# OpenDeck.net
KiCad netlist of a schematic drawn in EAGLE
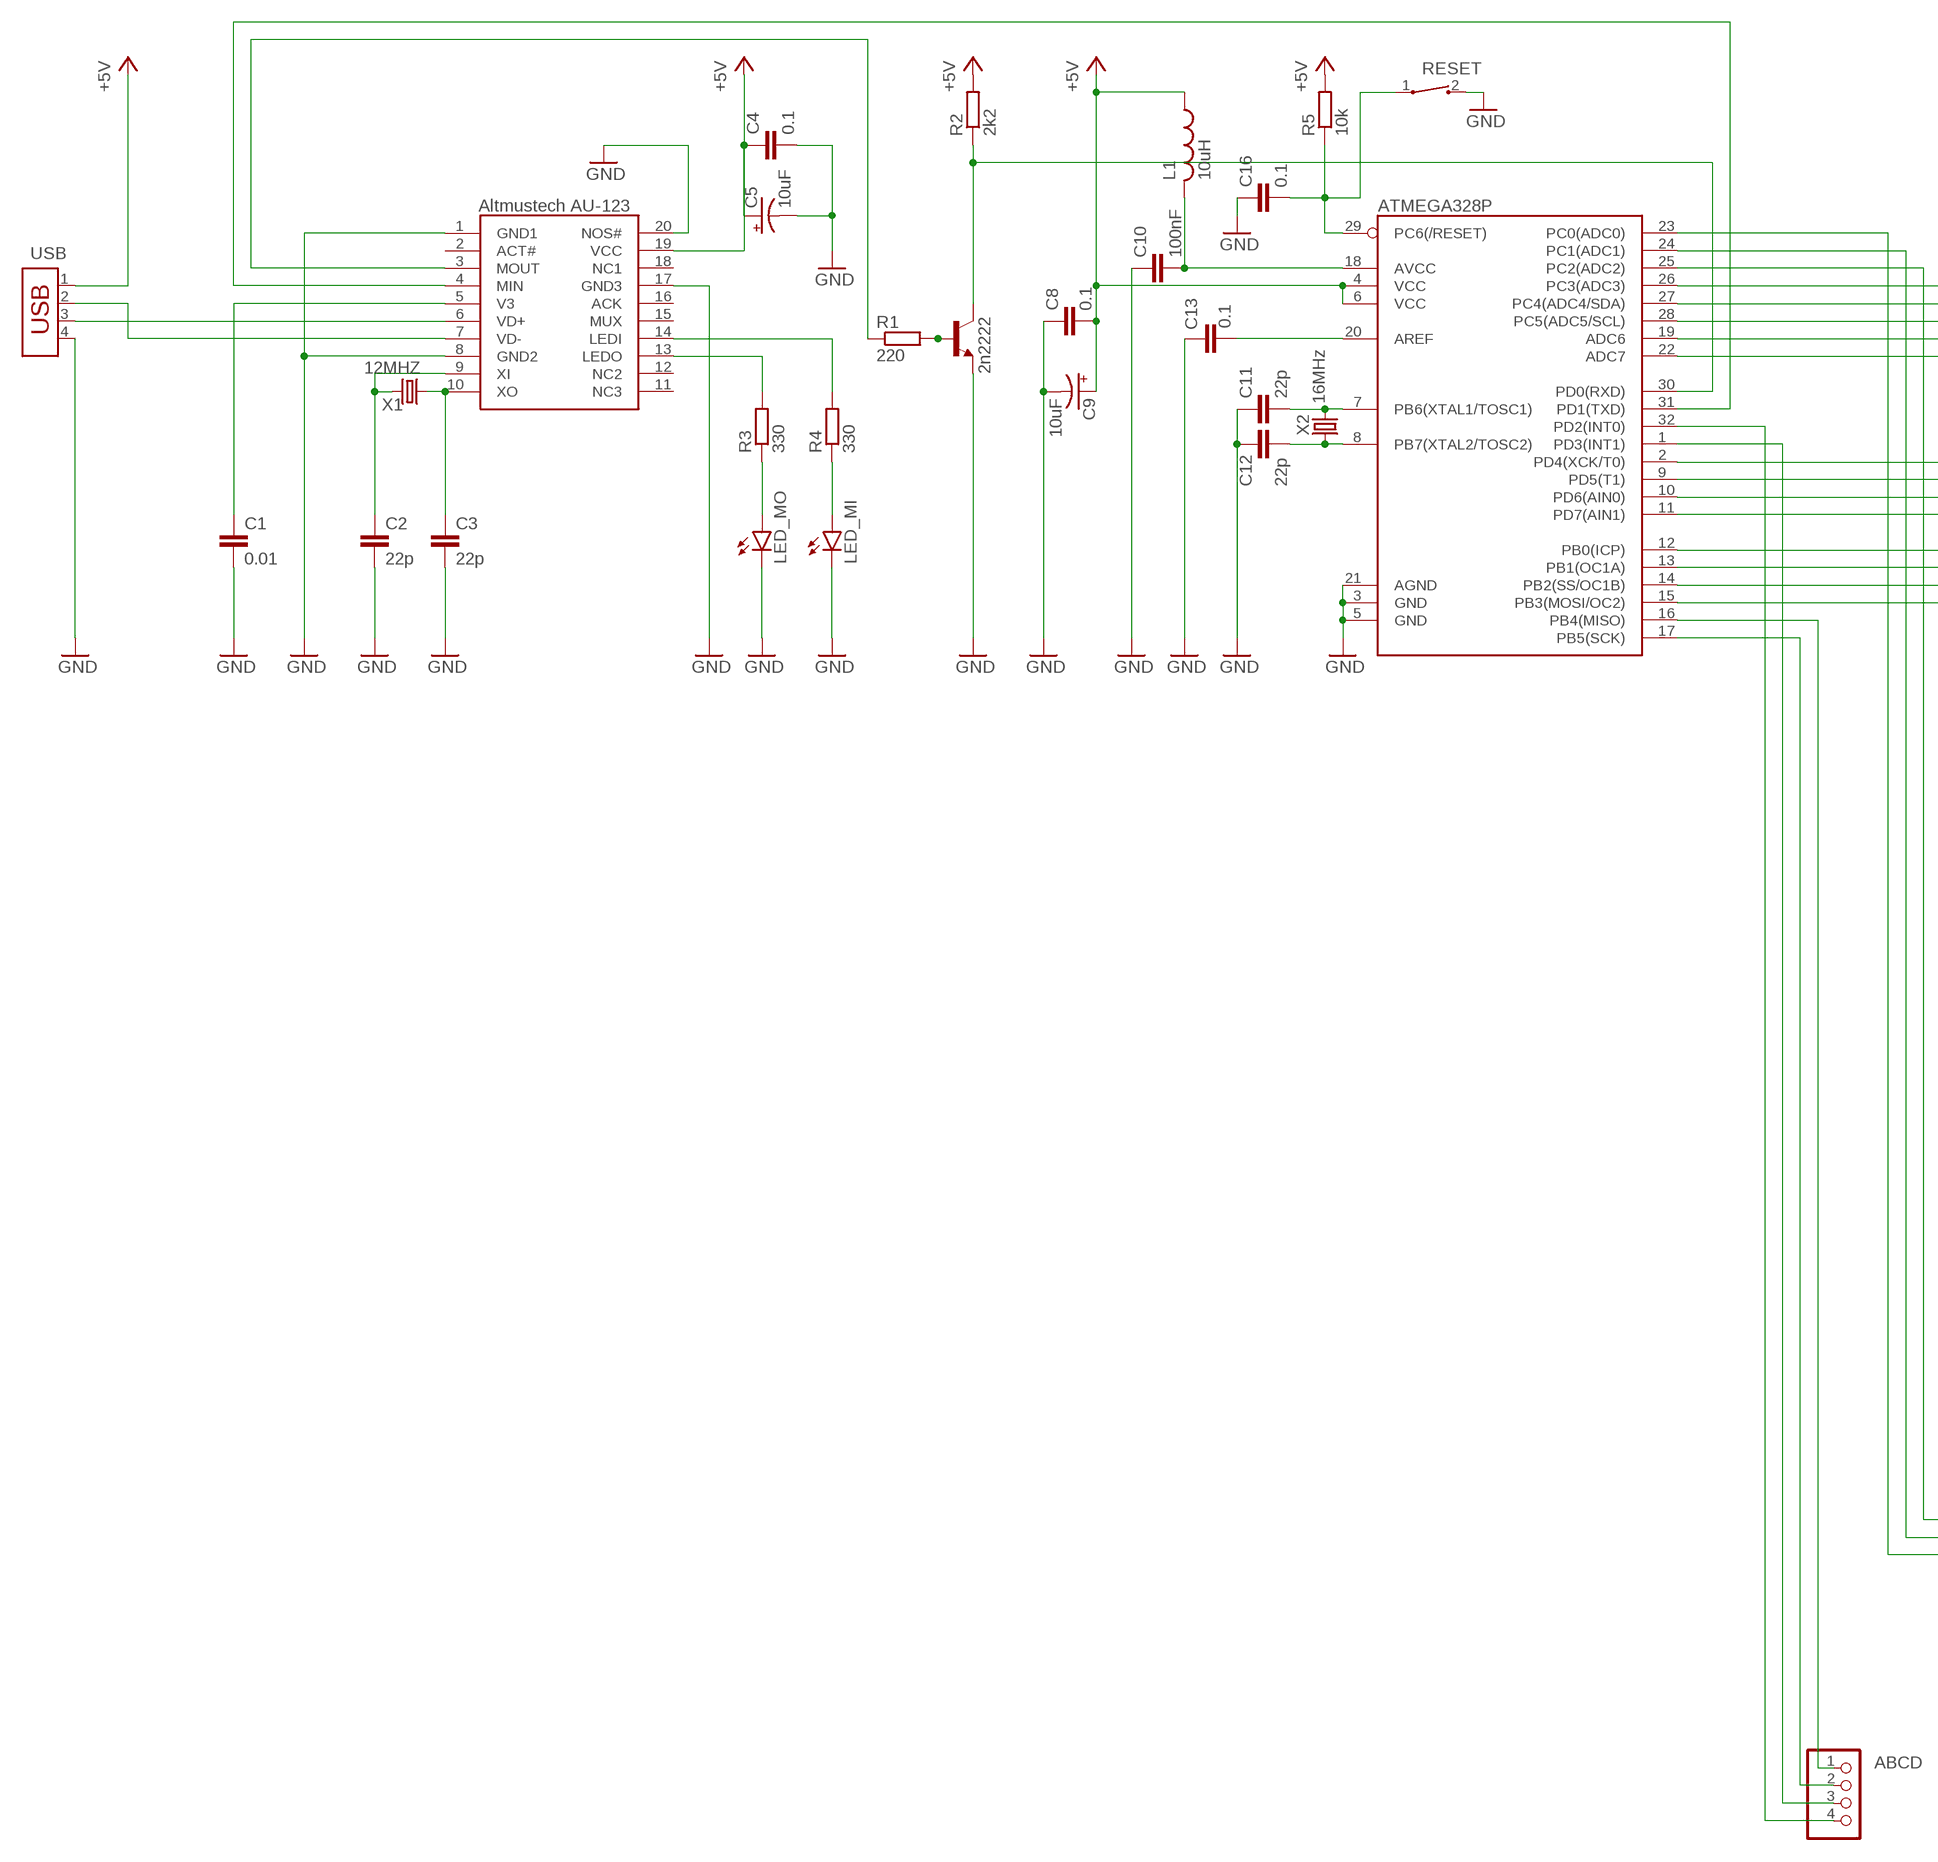
[diagram p0: schematic, sheet 1, part 1 of 2]
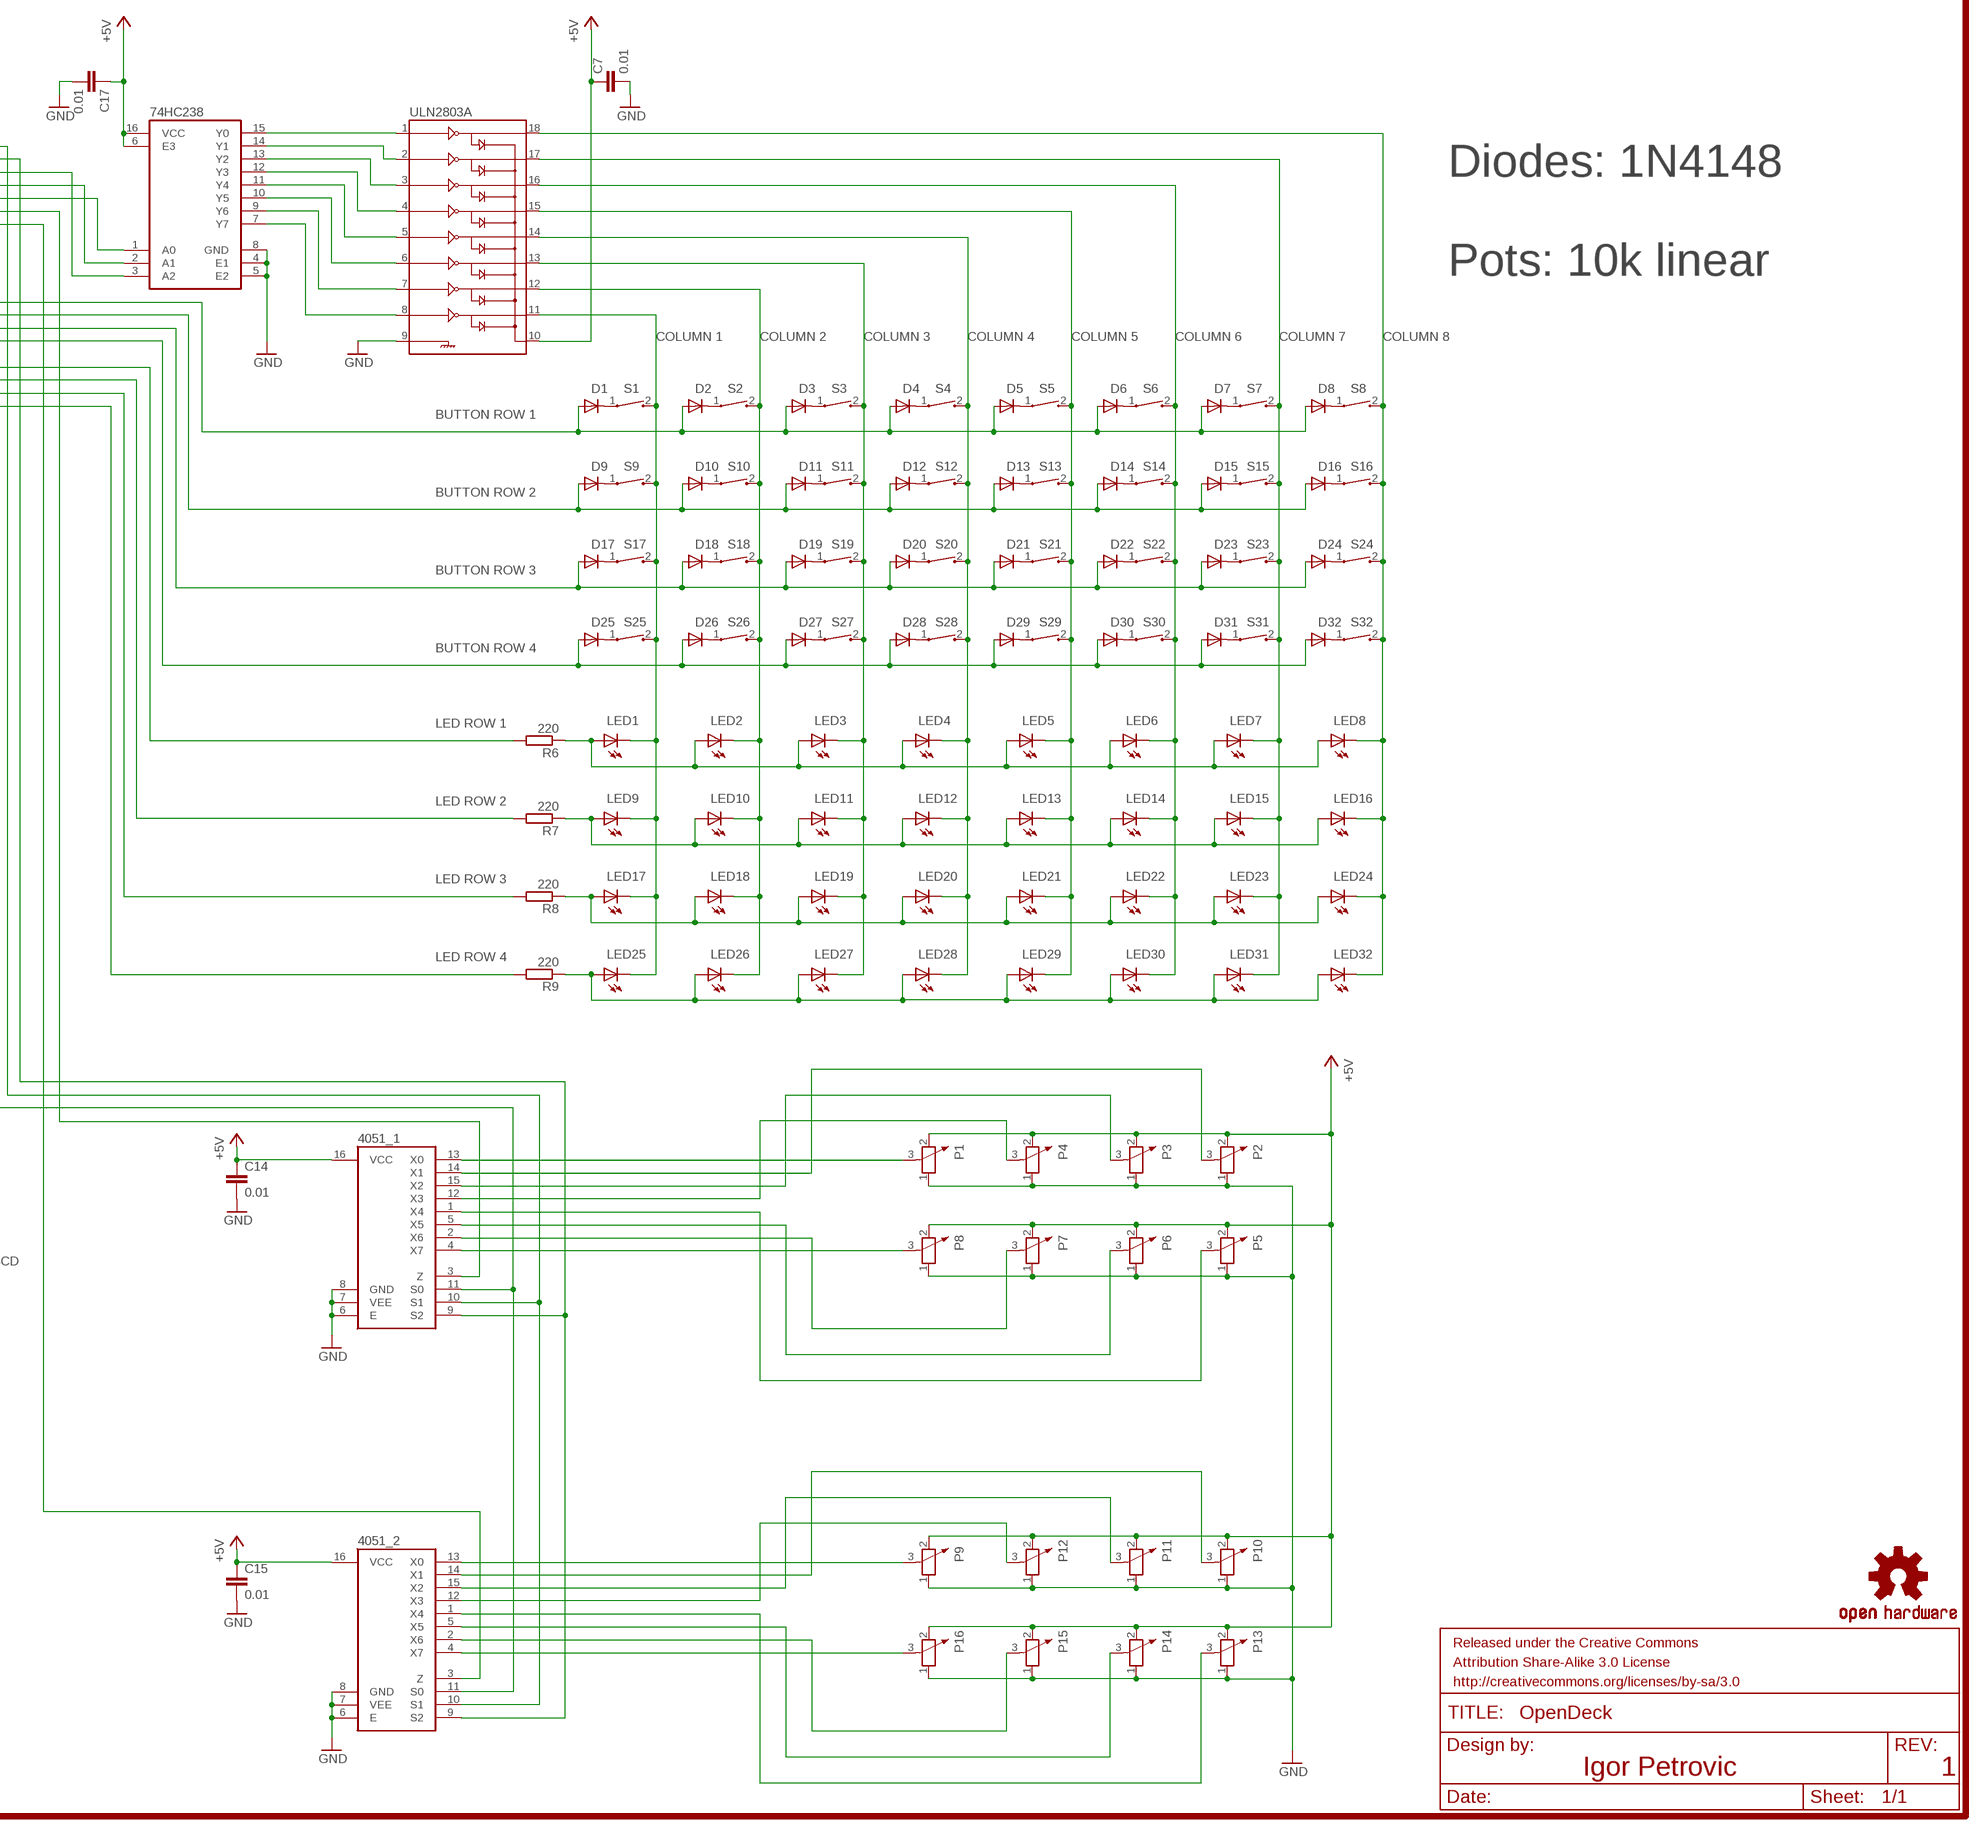
[diagram p1: schematic, sheet 1, part 2 of 2]

(export (version "E")
  (design (tool "Eeschema 10.0.6"))
  (components
    (comp (ref "74HC238")
      (value "74HC238-FULL")
      (footprint "eagle-import:DIL16")
      (libsource (lib "eagle-import") (part "74HC238-FULL"))
    )
    (comp (ref "4051_1")
      (value "4051-FULL")
      (footprint "eagle-import:DIL16")
      (libsource (lib "eagle-import") (part "4051-FULL"))
    )
    (comp (ref "4051_2")
      (value "4051-FULL")
      (footprint "eagle-import:DIL16")
      (libsource (lib "eagle-import") (part "4051-FULL"))
    )
    (comp (ref "ABCD")
      (value "PINHD-1X4")
      (footprint "eagle-import:1X04")
      (libsource (lib "eagle-import") (part "PINHD-1X4"))
    )
    (comp (ref "ALTMUSTECH_AU123")
      (value "XC18V01_SO20")
      (footprint "eagle-import:SOP20")
      (libsource (lib "eagle-import") (part "XC18V01_SO20"))
    )
    (comp (ref "C1")
      (value "0.01")
      (footprint "eagle-import:C025-025X050")
      (libsource (lib "eagle-import") (part "C-EU025-025X050"))
    )
    (comp (ref "C2")
      (value "22p")
      (footprint "eagle-import:C025-025X050")
      (libsource (lib "eagle-import") (part "C-EU025-025X050"))
    )
    (comp (ref "C3")
      (value "22p")
      (footprint "eagle-import:C025-025X050")
      (libsource (lib "eagle-import") (part "C-EU025-025X050"))
    )
    (comp (ref "C4")
      (value "0.1")
      (footprint "eagle-import:C025-025X050")
      (libsource (lib "eagle-import") (part "C-EU025-025X050"))
    )
    (comp (ref "C5")
      (value "10uF")
      (footprint "eagle-import:PANASONIC_H13")
      (libsource (lib "eagle-import") (part "100UF-63V-20%(ELECT)"))
    )
    (comp (ref "C7")
      (value "0.01")
      (footprint "eagle-import:C025-025X050")
      (libsource (lib "eagle-import") (part "C-EU025-025X050"))
    )
    (comp (ref "C8")
      (value "0.1")
      (footprint "eagle-import:C025-025X050")
      (libsource (lib "eagle-import") (part "C-EU025-025X050"))
    )
    (comp (ref "C9")
      (value "10uF")
      (footprint "eagle-import:PANASONIC_H13")
      (libsource (lib "eagle-import") (part "100UF-63V-20%(ELECT)"))
    )
    (comp (ref "C10")
      (value "100nF")
      (footprint "eagle-import:C025-025X050")
      (libsource (lib "eagle-import") (part "C-EU025-025X050"))
    )
    (comp (ref "C11")
      (value "22p")
      (footprint "eagle-import:C025-025X050")
      (libsource (lib "eagle-import") (part "C-EU025-025X050"))
    )
    (comp (ref "C12")
      (value "22p")
      (footprint "eagle-import:C025-025X050")
      (libsource (lib "eagle-import") (part "C-EU025-025X050"))
    )
    (comp (ref "C13")
      (value "0.1")
      (footprint "eagle-import:C025-025X050")
      (libsource (lib "eagle-import") (part "C-EU025-025X050"))
    )
    (comp (ref "C14")
      (value "0.01")
      (footprint "eagle-import:C025-025X050")
      (libsource (lib "eagle-import") (part "C-EU025-025X050"))
    )
    (comp (ref "C15")
      (value "0.01")
      (footprint "eagle-import:C025-025X050")
      (libsource (lib "eagle-import") (part "C-EU025-025X050"))
    )
    (comp (ref "C16")
      (value "0.1")
      (footprint "eagle-import:C025-025X050")
      (libsource (lib "eagle-import") (part "C-EU025-025X050"))
    )
    (comp (ref "C17")
      (value "0.01")
      (footprint "eagle-import:C025-025X050")
      (libsource (lib "eagle-import") (part "C-EU025-025X050"))
    )
    (comp (ref "D1")
      (value "1N4148DO35-10")
      (footprint "eagle-import:DO35-10")
      (libsource (lib "eagle-import") (part "1N4148DO35-10"))
    )
    (comp (ref "D2")
      (value "1N4148DO35-10")
      (footprint "eagle-import:DO35-10")
      (libsource (lib "eagle-import") (part "1N4148DO35-10"))
    )
    (comp (ref "D3")
      (value "1N4148DO35-10")
      (footprint "eagle-import:DO35-10")
      (libsource (lib "eagle-import") (part "1N4148DO35-10"))
    )
    (comp (ref "D4")
      (value "1N4148DO35-10")
      (footprint "eagle-import:DO35-10")
      (libsource (lib "eagle-import") (part "1N4148DO35-10"))
    )
    (comp (ref "D5")
      (value "1N4148DO35-10")
      (footprint "eagle-import:DO35-10")
      (libsource (lib "eagle-import") (part "1N4148DO35-10"))
    )
    (comp (ref "D6")
      (value "1N4148DO35-10")
      (footprint "eagle-import:DO35-10")
      (libsource (lib "eagle-import") (part "1N4148DO35-10"))
    )
    (comp (ref "D7")
      (value "1N4148DO35-10")
      (footprint "eagle-import:DO35-10")
      (libsource (lib "eagle-import") (part "1N4148DO35-10"))
    )
    (comp (ref "D8")
      (value "1N4148DO35-10")
      (footprint "eagle-import:DO35-10")
      (libsource (lib "eagle-import") (part "1N4148DO35-10"))
    )
    (comp (ref "D9")
      (value "1N4148DO35-10")
      (footprint "eagle-import:DO35-10")
      (libsource (lib "eagle-import") (part "1N4148DO35-10"))
    )
    (comp (ref "D10")
      (value "1N4148DO35-10")
      (footprint "eagle-import:DO35-10")
      (libsource (lib "eagle-import") (part "1N4148DO35-10"))
    )
    (comp (ref "D11")
      (value "1N4148DO35-10")
      (footprint "eagle-import:DO35-10")
      (libsource (lib "eagle-import") (part "1N4148DO35-10"))
    )
    (comp (ref "D12")
      (value "1N4148DO35-10")
      (footprint "eagle-import:DO35-10")
      (libsource (lib "eagle-import") (part "1N4148DO35-10"))
    )
    (comp (ref "D13")
      (value "1N4148DO35-10")
      (footprint "eagle-import:DO35-10")
      (libsource (lib "eagle-import") (part "1N4148DO35-10"))
    )
    (comp (ref "D14")
      (value "1N4148DO35-10")
      (footprint "eagle-import:DO35-10")
      (libsource (lib "eagle-import") (part "1N4148DO35-10"))
    )
    (comp (ref "D15")
      (value "1N4148DO35-10")
      (footprint "eagle-import:DO35-10")
      (libsource (lib "eagle-import") (part "1N4148DO35-10"))
    )
    (comp (ref "D16")
      (value "1N4148DO35-10")
      (footprint "eagle-import:DO35-10")
      (libsource (lib "eagle-import") (part "1N4148DO35-10"))
    )
    (comp (ref "D17")
      (value "1N4148DO35-10")
      (footprint "eagle-import:DO35-10")
      (libsource (lib "eagle-import") (part "1N4148DO35-10"))
    )
    (comp (ref "D18")
      (value "1N4148DO35-10")
      (footprint "eagle-import:DO35-10")
      (libsource (lib "eagle-import") (part "1N4148DO35-10"))
    )
    (comp (ref "D19")
      (value "1N4148DO35-10")
      (footprint "eagle-import:DO35-10")
      (libsource (lib "eagle-import") (part "1N4148DO35-10"))
    )
    (comp (ref "D20")
      (value "1N4148DO35-10")
      (footprint "eagle-import:DO35-10")
      (libsource (lib "eagle-import") (part "1N4148DO35-10"))
    )
    (comp (ref "D21")
      (value "1N4148DO35-10")
      (footprint "eagle-import:DO35-10")
      (libsource (lib "eagle-import") (part "1N4148DO35-10"))
    )
    (comp (ref "D22")
      (value "1N4148DO35-10")
      (footprint "eagle-import:DO35-10")
      (libsource (lib "eagle-import") (part "1N4148DO35-10"))
    )
    (comp (ref "D23")
      (value "1N4148DO35-10")
      (footprint "eagle-import:DO35-10")
      (libsource (lib "eagle-import") (part "1N4148DO35-10"))
    )
    (comp (ref "D24")
      (value "1N4148DO35-10")
      (footprint "eagle-import:DO35-10")
      (libsource (lib "eagle-import") (part "1N4148DO35-10"))
    )
    (comp (ref "D25")
      (value "1N4148DO35-10")
      (footprint "eagle-import:DO35-10")
      (libsource (lib "eagle-import") (part "1N4148DO35-10"))
    )
    (comp (ref "D26")
      (value "1N4148DO35-10")
      (footprint "eagle-import:DO35-10")
      (libsource (lib "eagle-import") (part "1N4148DO35-10"))
    )
    (comp (ref "D27")
      (value "1N4148DO35-10")
      (footprint "eagle-import:DO35-10")
      (libsource (lib "eagle-import") (part "1N4148DO35-10"))
    )
    (comp (ref "D28")
      (value "1N4148DO35-10")
      (footprint "eagle-import:DO35-10")
      (libsource (lib "eagle-import") (part "1N4148DO35-10"))
    )
    (comp (ref "D29")
      (value "1N4148DO35-10")
      (footprint "eagle-import:DO35-10")
      (libsource (lib "eagle-import") (part "1N4148DO35-10"))
    )
    (comp (ref "D30")
      (value "1N4148DO35-10")
      (footprint "eagle-import:DO35-10")
      (libsource (lib "eagle-import") (part "1N4148DO35-10"))
    )
    (comp (ref "D31")
      (value "1N4148DO35-10")
      (footprint "eagle-import:DO35-10")
      (libsource (lib "eagle-import") (part "1N4148DO35-10"))
    )
    (comp (ref "D32")
      (value "1N4148DO35-10")
      (footprint "eagle-import:DO35-10")
      (libsource (lib "eagle-import") (part "1N4148DO35-10"))
    )
    (comp (ref "FRAME1")
      (value "FRAME-LETTER")
      (footprint "eagle-import:CREATIVE_COMMONS")
      (libsource (lib "eagle-import") (part "FRAME-LETTER"))
    )
    (comp (ref "L1")
      (value "10uH")
      (footprint "eagle-import:0204_7")
      (libsource (lib "eagle-import") (part "L-US0204/7"))
    )
    (comp (ref "LED1")
      (value "LAW51M")
      (footprint "eagle-import:W51")
      (libsource (lib "eagle-import") (part "W51MLA"))
    )
    (comp (ref "LED2")
      (value "LAW51M")
      (footprint "eagle-import:W51")
      (libsource (lib "eagle-import") (part "W51MLA"))
    )
    (comp (ref "LED3")
      (value "LAW51M")
      (footprint "eagle-import:W51")
      (libsource (lib "eagle-import") (part "W51MLA"))
    )
    (comp (ref "LED4")
      (value "LAW51M")
      (footprint "eagle-import:W51")
      (libsource (lib "eagle-import") (part "W51MLA"))
    )
    (comp (ref "LED5")
      (value "LAW51M")
      (footprint "eagle-import:W51")
      (libsource (lib "eagle-import") (part "W51MLA"))
    )
    (comp (ref "LED6")
      (value "LAW51M")
      (footprint "eagle-import:W51")
      (libsource (lib "eagle-import") (part "W51MLA"))
    )
    (comp (ref "LED7")
      (value "LAW51M")
      (footprint "eagle-import:W51")
      (libsource (lib "eagle-import") (part "W51MLA"))
    )
    (comp (ref "LED8")
      (value "LAW51M")
      (footprint "eagle-import:W51")
      (libsource (lib "eagle-import") (part "W51MLA"))
    )
    (comp (ref "LED9")
      (value "LAW51M")
      (footprint "eagle-import:W51")
      (libsource (lib "eagle-import") (part "W51MLA"))
    )
    (comp (ref "LED10")
      (value "LAW51M")
      (footprint "eagle-import:W51")
      (libsource (lib "eagle-import") (part "W51MLA"))
    )
    (comp (ref "LED11")
      (value "LAW51M")
      (footprint "eagle-import:W51")
      (libsource (lib "eagle-import") (part "W51MLA"))
    )
    (comp (ref "LED12")
      (value "LAW51M")
      (footprint "eagle-import:W51")
      (libsource (lib "eagle-import") (part "W51MLA"))
    )
    (comp (ref "LED13")
      (value "LAW51M")
      (footprint "eagle-import:W51")
      (libsource (lib "eagle-import") (part "W51MLA"))
    )
    (comp (ref "LED14")
      (value "LAW51M")
      (footprint "eagle-import:W51")
      (libsource (lib "eagle-import") (part "W51MLA"))
    )
    (comp (ref "LED15")
      (value "LAW51M")
      (footprint "eagle-import:W51")
      (libsource (lib "eagle-import") (part "W51MLA"))
    )
    (comp (ref "LED16")
      (value "LAW51M")
      (footprint "eagle-import:W51")
      (libsource (lib "eagle-import") (part "W51MLA"))
    )
    (comp (ref "LED17")
      (value "LAW51M")
      (footprint "eagle-import:W51")
      (libsource (lib "eagle-import") (part "W51MLA"))
    )
    (comp (ref "LED18")
      (value "LAW51M")
      (footprint "eagle-import:W51")
      (libsource (lib "eagle-import") (part "W51MLA"))
    )
    (comp (ref "LED19")
      (value "LAW51M")
      (footprint "eagle-import:W51")
      (libsource (lib "eagle-import") (part "W51MLA"))
    )
    (comp (ref "LED20")
      (value "LAW51M")
      (footprint "eagle-import:W51")
      (libsource (lib "eagle-import") (part "W51MLA"))
    )
    (comp (ref "LED21")
      (value "LAW51M")
      (footprint "eagle-import:W51")
      (libsource (lib "eagle-import") (part "W51MLA"))
    )
    (comp (ref "LED22")
      (value "LAW51M")
      (footprint "eagle-import:W51")
      (libsource (lib "eagle-import") (part "W51MLA"))
    )
    (comp (ref "LED23")
      (value "LAW51M")
      (footprint "eagle-import:W51")
      (libsource (lib "eagle-import") (part "W51MLA"))
    )
    (comp (ref "LED24")
      (value "LAW51M")
      (footprint "eagle-import:W51")
      (libsource (lib "eagle-import") (part "W51MLA"))
    )
    (comp (ref "LED25")
      (value "LAW51M")
      (footprint "eagle-import:W51")
      (libsource (lib "eagle-import") (part "W51MLA"))
    )
    (comp (ref "LED26")
      (value "LAW51M")
      (footprint "eagle-import:W51")
      (libsource (lib "eagle-import") (part "W51MLA"))
    )
    (comp (ref "LED27")
      (value "LAW51M")
      (footprint "eagle-import:W51")
      (libsource (lib "eagle-import") (part "W51MLA"))
    )
    (comp (ref "LED28")
      (value "LAW51M")
      (footprint "eagle-import:W51")
      (libsource (lib "eagle-import") (part "W51MLA"))
    )
    (comp (ref "LED29")
      (value "LAW51M")
      (footprint "eagle-import:W51")
      (libsource (lib "eagle-import") (part "W51MLA"))
    )
    (comp (ref "LED30")
      (value "LAW51M")
      (footprint "eagle-import:W51")
      (libsource (lib "eagle-import") (part "W51MLA"))
    )
    (comp (ref "LED31")
      (value "LAW51M")
      (footprint "eagle-import:W51")
      (libsource (lib "eagle-import") (part "W51MLA"))
    )
    (comp (ref "LED32")
      (value "LAW51M")
      (footprint "eagle-import:W51")
      (libsource (lib "eagle-import") (part "W51MLA"))
    )
    (comp (ref "LED_MI")
      (value "LED3MM")
      (footprint "eagle-import:LED3MM")
      (libsource (lib "eagle-import") (part "LED3MM"))
    )
    (comp (ref "LED_MO")
      (value "LED3MM")
      (footprint "eagle-import:LED3MM")
      (libsource (lib "eagle-import") (part "LED3MM"))
    )
    (comp (ref "P1")
      (value "10k")
      (footprint "eagle-import:PT-10")
      (libsource (lib "eagle-import") (part "POTENTIOMETER_PT-10"))
    )
    (comp (ref "P2")
      (value "10k")
      (footprint "eagle-import:PT-10")
      (libsource (lib "eagle-import") (part "POTENTIOMETER_PT-10"))
    )
    (comp (ref "P3")
      (value "10k")
      (footprint "eagle-import:PT-10")
      (libsource (lib "eagle-import") (part "POTENTIOMETER_PT-10"))
    )
    (comp (ref "P4")
      (value "10k")
      (footprint "eagle-import:PT-10")
      (libsource (lib "eagle-import") (part "POTENTIOMETER_PT-10"))
    )
    (comp (ref "P5")
      (value "10k")
      (footprint "eagle-import:PT-10")
      (libsource (lib "eagle-import") (part "POTENTIOMETER_PT-10"))
    )
    (comp (ref "P6")
      (value "10k")
      (footprint "eagle-import:PT-10")
      (libsource (lib "eagle-import") (part "POTENTIOMETER_PT-10"))
    )
    (comp (ref "P7")
      (value "10k")
      (footprint "eagle-import:PT-10")
      (libsource (lib "eagle-import") (part "POTENTIOMETER_PT-10"))
    )
    (comp (ref "P8")
      (value "10k")
      (footprint "eagle-import:PT-10")
      (libsource (lib "eagle-import") (part "POTENTIOMETER_PT-10"))
    )
    (comp (ref "P9")
      (value "10k")
      (footprint "eagle-import:PT-10")
      (libsource (lib "eagle-import") (part "POTENTIOMETER_PT-10"))
    )
    (comp (ref "P10")
      (value "10k")
      (footprint "eagle-import:PT-10")
      (libsource (lib "eagle-import") (part "POTENTIOMETER_PT-10"))
    )
    (comp (ref "P11")
      (value "10k")
      (footprint "eagle-import:PT-10")
      (libsource (lib "eagle-import") (part "POTENTIOMETER_PT-10"))
    )
    (comp (ref "P12")
      (value "10k")
      (footprint "eagle-import:PT-10")
      (libsource (lib "eagle-import") (part "POTENTIOMETER_PT-10"))
    )
    (comp (ref "P13")
      (value "10k")
      (footprint "eagle-import:PT-10")
      (libsource (lib "eagle-import") (part "POTENTIOMETER_PT-10"))
    )
    (comp (ref "P14")
      (value "10k")
      (footprint "eagle-import:PT-10")
      (libsource (lib "eagle-import") (part "POTENTIOMETER_PT-10"))
    )
    (comp (ref "P15")
      (value "10k")
      (footprint "eagle-import:PT-10")
      (libsource (lib "eagle-import") (part "POTENTIOMETER_PT-10"))
    )
    (comp (ref "P16")
      (value "10k")
      (footprint "eagle-import:PT-10")
      (libsource (lib "eagle-import") (part "POTENTIOMETER_PT-10"))
    )
    (comp (ref "Q1")
      (value "2n2222")
      (footprint "eagle-import:TO-92")
      (libsource (lib "eagle-import") (part "TRANSISTOR_NPN2N3904"))
    )
    (comp (ref "R1")
      (value "220")
      (footprint "eagle-import:0204_7")
      (libsource (lib "eagle-import") (part "R-EU_0204/7"))
    )
    (comp (ref "R2")
      (value "2k2")
      (footprint "eagle-import:0204_7")
      (libsource (lib "eagle-import") (part "R-EU_0204/7"))
    )
    (comp (ref "R3")
      (value "330")
      (footprint "eagle-import:0204_7")
      (libsource (lib "eagle-import") (part "R-EU_0204/7"))
    )
    (comp (ref "R4")
      (value "330")
      (footprint "eagle-import:0204_7")
      (libsource (lib "eagle-import") (part "R-EU_0204/7"))
    )
    (comp (ref "R5")
      (value "10k")
      (footprint "eagle-import:0204_7")
      (libsource (lib "eagle-import") (part "R-EU_0204/7"))
    )
    (comp (ref "R6")
      (value "220")
      (footprint "eagle-import:0204_7")
      (libsource (lib "eagle-import") (part "R-EU_0204/7"))
    )
    (comp (ref "R7")
      (value "220")
      (footprint "eagle-import:0204_7")
      (libsource (lib "eagle-import") (part "R-EU_0204/7"))
    )
    (comp (ref "R8")
      (value "220")
      (footprint "eagle-import:0204_7")
      (libsource (lib "eagle-import") (part "R-EU_0204/7"))
    )
    (comp (ref "R9")
      (value "220")
      (footprint "eagle-import:0204_7")
      (libsource (lib "eagle-import") (part "R-EU_0204/7"))
    )
    (comp (ref "RESET")
      (value "CT10-XXXX-A2")
      (footprint "eagle-import:CT10-XXXX-A2")
      (libsource (lib "eagle-import") (part "CT10-XXXX-A2"))
    )
    (comp (ref "S1")
      (value "CT10-XXXX-A2")
      (footprint "eagle-import:CT10-XXXX-A2")
      (libsource (lib "eagle-import") (part "CT10-XXXX-A2"))
    )
    (comp (ref "S2")
      (value "CT10-XXXX-A2")
      (footprint "eagle-import:CT10-XXXX-A2")
      (libsource (lib "eagle-import") (part "CT10-XXXX-A2"))
    )
    (comp (ref "S3")
      (value "CT10-XXXX-A2")
      (footprint "eagle-import:CT10-XXXX-A2")
      (libsource (lib "eagle-import") (part "CT10-XXXX-A2"))
    )
    (comp (ref "S4")
      (value "CT10-XXXX-A2")
      (footprint "eagle-import:CT10-XXXX-A2")
      (libsource (lib "eagle-import") (part "CT10-XXXX-A2"))
    )
    (comp (ref "S5")
      (value "CT10-XXXX-A2")
      (footprint "eagle-import:CT10-XXXX-A2")
      (libsource (lib "eagle-import") (part "CT10-XXXX-A2"))
    )
    (comp (ref "S6")
      (value "CT10-XXXX-A2")
      (footprint "eagle-import:CT10-XXXX-A2")
      (libsource (lib "eagle-import") (part "CT10-XXXX-A2"))
    )
    (comp (ref "S7")
      (value "CT10-XXXX-A2")
      (footprint "eagle-import:CT10-XXXX-A2")
      (libsource (lib "eagle-import") (part "CT10-XXXX-A2"))
    )
    (comp (ref "S8")
      (value "CT10-XXXX-A2")
      (footprint "eagle-import:CT10-XXXX-A2")
      (libsource (lib "eagle-import") (part "CT10-XXXX-A2"))
    )
    (comp (ref "S9")
      (value "CT10-XXXX-A2")
      (footprint "eagle-import:CT10-XXXX-A2")
      (libsource (lib "eagle-import") (part "CT10-XXXX-A2"))
    )
    (comp (ref "S10")
      (value "CT10-XXXX-A2")
      (footprint "eagle-import:CT10-XXXX-A2")
      (libsource (lib "eagle-import") (part "CT10-XXXX-A2"))
    )
    (comp (ref "S11")
      (value "CT10-XXXX-A2")
      (footprint "eagle-import:CT10-XXXX-A2")
      (libsource (lib "eagle-import") (part "CT10-XXXX-A2"))
    )
    (comp (ref "S12")
      (value "CT10-XXXX-A2")
      (footprint "eagle-import:CT10-XXXX-A2")
      (libsource (lib "eagle-import") (part "CT10-XXXX-A2"))
    )
    (comp (ref "S13")
      (value "CT10-XXXX-A2")
      (footprint "eagle-import:CT10-XXXX-A2")
      (libsource (lib "eagle-import") (part "CT10-XXXX-A2"))
    )
    (comp (ref "S14")
      (value "CT10-XXXX-A2")
      (footprint "eagle-import:CT10-XXXX-A2")
      (libsource (lib "eagle-import") (part "CT10-XXXX-A2"))
    )
    (comp (ref "S15")
      (value "CT10-XXXX-A2")
      (footprint "eagle-import:CT10-XXXX-A2")
      (libsource (lib "eagle-import") (part "CT10-XXXX-A2"))
    )
    (comp (ref "S16")
      (value "CT10-XXXX-A2")
      (footprint "eagle-import:CT10-XXXX-A2")
      (libsource (lib "eagle-import") (part "CT10-XXXX-A2"))
    )
    (comp (ref "S17")
      (value "CT10-XXXX-A2")
      (footprint "eagle-import:CT10-XXXX-A2")
      (libsource (lib "eagle-import") (part "CT10-XXXX-A2"))
    )
    (comp (ref "S18")
      (value "CT10-XXXX-A2")
      (footprint "eagle-import:CT10-XXXX-A2")
      (libsource (lib "eagle-import") (part "CT10-XXXX-A2"))
    )
    (comp (ref "S19")
      (value "CT10-XXXX-A2")
      (footprint "eagle-import:CT10-XXXX-A2")
      (libsource (lib "eagle-import") (part "CT10-XXXX-A2"))
    )
    (comp (ref "S20")
      (value "CT10-XXXX-A2")
      (footprint "eagle-import:CT10-XXXX-A2")
      (libsource (lib "eagle-import") (part "CT10-XXXX-A2"))
    )
    (comp (ref "S21")
      (value "CT10-XXXX-A2")
      (footprint "eagle-import:CT10-XXXX-A2")
      (libsource (lib "eagle-import") (part "CT10-XXXX-A2"))
    )
    (comp (ref "S22")
      (value "CT10-XXXX-A2")
      (footprint "eagle-import:CT10-XXXX-A2")
      (libsource (lib "eagle-import") (part "CT10-XXXX-A2"))
    )
    (comp (ref "S23")
      (value "CT10-XXXX-A2")
      (footprint "eagle-import:CT10-XXXX-A2")
      (libsource (lib "eagle-import") (part "CT10-XXXX-A2"))
    )
    (comp (ref "S24")
      (value "CT10-XXXX-A2")
      (footprint "eagle-import:CT10-XXXX-A2")
      (libsource (lib "eagle-import") (part "CT10-XXXX-A2"))
    )
    (comp (ref "S25")
      (value "CT10-XXXX-A2")
      (footprint "eagle-import:CT10-XXXX-A2")
      (libsource (lib "eagle-import") (part "CT10-XXXX-A2"))
    )
    (comp (ref "S26")
      (value "CT10-XXXX-A2")
      (footprint "eagle-import:CT10-XXXX-A2")
      (libsource (lib "eagle-import") (part "CT10-XXXX-A2"))
    )
    (comp (ref "S27")
      (value "CT10-XXXX-A2")
      (footprint "eagle-import:CT10-XXXX-A2")
      (libsource (lib "eagle-import") (part "CT10-XXXX-A2"))
    )
    (comp (ref "S28")
      (value "CT10-XXXX-A2")
      (footprint "eagle-import:CT10-XXXX-A2")
      (libsource (lib "eagle-import") (part "CT10-XXXX-A2"))
    )
    (comp (ref "S29")
      (value "CT10-XXXX-A2")
      (footprint "eagle-import:CT10-XXXX-A2")
      (libsource (lib "eagle-import") (part "CT10-XXXX-A2"))
    )
    (comp (ref "S30")
      (value "CT10-XXXX-A2")
      (footprint "eagle-import:CT10-XXXX-A2")
      (libsource (lib "eagle-import") (part "CT10-XXXX-A2"))
    )
    (comp (ref "S31")
      (value "CT10-XXXX-A2")
      (footprint "eagle-import:CT10-XXXX-A2")
      (libsource (lib "eagle-import") (part "CT10-XXXX-A2"))
    )
    (comp (ref "S32")
      (value "CT10-XXXX-A2")
      (footprint "eagle-import:CT10-XXXX-A2")
      (libsource (lib "eagle-import") (part "CT10-XXXX-A2"))
    )
    (comp (ref "U$3")
      (value "OSHW-LOGOS")
      (footprint "eagle-import:OSHW-LOGO-S")
      (libsource (lib "eagle-import") (part "OSHW-LOGOS"))
    )
    (comp (ref "U2")
      (value "ATMEGA328P")
      (footprint "eagle-import:TQFP32-08")
      (libsource (lib "eagle-import") (part "ATMEGA328_SMT"))
    )
    (comp (ref "ULN2803A")
      (value "ULN2803DIP")
      (footprint "eagle-import:DIL18")
      (libsource (lib "eagle-import") (part "ULN2803DIP"))
    )
    (comp (ref "USB")
      (value "USB-787616")
      (footprint "eagle-import:USB")
      (libsource (lib "eagle-import") (part "USB-787616"))
    )
    (comp (ref "X1")
      (value "12MHZ")
      (footprint "eagle-import:HC49US")
      (libsource (lib "eagle-import") (part "CRYSTALHC49US"))
    )
    (comp (ref "X2")
      (value "16MHz")
      (footprint "eagle-import:HC49US")
      (libsource (lib "eagle-import") (part "CRYSTALHC49US"))
    )
  )
  (nets
    (net (code "1") (name "+5V") (class "Default")
      (node (ref "4051_1") (pin "16") (pinfunction "VCC_16") (pintype "power_in"))
      (node (ref "4051_2") (pin "16") (pinfunction "VCC_16") (pintype "power_in"))
      (node (ref "74HC238") (pin "16") (pinfunction "VCC_16") (pintype "power_in"))
      (node (ref "74HC238") (pin "6") (pinfunction "E3_6") (pintype "input"))
      (node (ref "ALTMUSTECH_AU123") (pin "19") (pinfunction "VCC_19") (pintype "power_in"))
      (node (ref "C14") (pin "1") (pinfunction "1_1") (pintype "passive"))
      (node (ref "C15") (pin "1") (pinfunction "1_1") (pintype "passive"))
      (node (ref "C17") (pin "1") (pinfunction "1_1") (pintype "passive"))
      (node (ref "C4") (pin "1") (pinfunction "1_1") (pintype "passive"))
      (node (ref "C5") (pin "+") (pinfunction "+_+") (pintype "passive"))
      (node (ref "C7") (pin "1") (pinfunction "1_1") (pintype "passive"))
      (node (ref "C8") (pin "2") (pinfunction "2_2") (pintype "passive"))
      (node (ref "C9") (pin "+") (pinfunction "+_+") (pintype "passive"))
      (node (ref "L1") (pin "1") (pinfunction "1_1") (pintype "passive"))
      (node (ref "P1") (pin "2") (pinfunction "2_2") (pintype "passive"))
      (node (ref "P10") (pin "2") (pinfunction "2_2") (pintype "passive"))
      (node (ref "P11") (pin "2") (pinfunction "2_2") (pintype "passive"))
      (node (ref "P12") (pin "2") (pinfunction "2_2") (pintype "passive"))
      (node (ref "P13") (pin "2") (pinfunction "2_2") (pintype "passive"))
      (node (ref "P14") (pin "2") (pinfunction "2_2") (pintype "passive"))
      (node (ref "P15") (pin "2") (pinfunction "2_2") (pintype "passive"))
      (node (ref "P16") (pin "2") (pinfunction "2_2") (pintype "passive"))
      (node (ref "P2") (pin "2") (pinfunction "2_2") (pintype "passive"))
      (node (ref "P3") (pin "2") (pinfunction "2_2") (pintype "passive"))
      (node (ref "P4") (pin "2") (pinfunction "2_2") (pintype "passive"))
      (node (ref "P5") (pin "2") (pinfunction "2_2") (pintype "passive"))
      (node (ref "P6") (pin "2") (pinfunction "2_2") (pintype "passive"))
      (node (ref "P7") (pin "2") (pinfunction "2_2") (pintype "passive"))
      (node (ref "P8") (pin "2") (pinfunction "2_2") (pintype "passive"))
      (node (ref "P9") (pin "2") (pinfunction "2_2") (pintype "passive"))
      (node (ref "R2") (pin "2") (pinfunction "2_2") (pintype "passive"))
      (node (ref "R5") (pin "2") (pinfunction "2_2") (pintype "passive"))
      (node (ref "U2") (pin "4") (pinfunction "VCC_4") (pintype "bidirectional"))
      (node (ref "U2") (pin "6") (pinfunction "VCC_6") (pintype "bidirectional"))
      (node (ref "ULN2803A") (pin "10") (pinfunction "10_10") (pintype "bidirectional"))
      (node (ref "USB") (pin "1") (pinfunction "1_1") (pintype "passive"))
    )
    (net (code "2") (name "GND") (class "Default")
      (node (ref "4051_1") (pin "6") (pinfunction "E_6") (pintype "input"))
      (node (ref "4051_1") (pin "7") (pinfunction "VEE_7") (pintype "power_in"))
      (node (ref "4051_1") (pin "8") (pinfunction "GND_8") (pintype "power_in"))
      (node (ref "4051_2") (pin "6") (pinfunction "E_6") (pintype "input"))
      (node (ref "4051_2") (pin "7") (pinfunction "VEE_7") (pintype "power_in"))
      (node (ref "4051_2") (pin "8") (pinfunction "GND_8") (pintype "power_in"))
      (node (ref "74HC238") (pin "4") (pinfunction "E1_4") (pintype "input"))
      (node (ref "74HC238") (pin "5") (pinfunction "E2_5") (pintype "input"))
      (node (ref "74HC238") (pin "8") (pinfunction "GND_8") (pintype "power_in"))
      (node (ref "ALTMUSTECH_AU123") (pin "1") (pinfunction "GND1_1") (pintype "power_in"))
      (node (ref "ALTMUSTECH_AU123") (pin "17") (pinfunction "GND3_17") (pintype "power_in"))
      (node (ref "ALTMUSTECH_AU123") (pin "20") (pinfunction "NOS#_20") (pintype "input"))
      (node (ref "ALTMUSTECH_AU123") (pin "8") (pinfunction "GND2_8") (pintype "power_in"))
      (node (ref "C1") (pin "2") (pinfunction "2_2") (pintype "passive"))
      (node (ref "C10") (pin "1") (pinfunction "1_1") (pintype "passive"))
      (node (ref "C11") (pin "1") (pinfunction "1_1") (pintype "passive"))
      (node (ref "C12") (pin "2") (pinfunction "2_2") (pintype "passive"))
      (node (ref "C13") (pin "2") (pinfunction "2_2") (pintype "passive"))
      (node (ref "C14") (pin "2") (pinfunction "2_2") (pintype "passive"))
      (node (ref "C15") (pin "2") (pinfunction "2_2") (pintype "passive"))
      (node (ref "C16") (pin "1") (pinfunction "1_1") (pintype "passive"))
      (node (ref "C17") (pin "2") (pinfunction "2_2") (pintype "passive"))
      (node (ref "C2") (pin "2") (pinfunction "2_2") (pintype "passive"))
      (node (ref "C3") (pin "2") (pinfunction "2_2") (pintype "passive"))
      (node (ref "C4") (pin "2") (pinfunction "2_2") (pintype "passive"))
      (node (ref "C5") (pin "-") (pinfunction "-_-") (pintype "passive"))
      (node (ref "C7") (pin "2") (pinfunction "2_2") (pintype "passive"))
      (node (ref "C8") (pin "1") (pinfunction "1_1") (pintype "passive"))
      (node (ref "C9") (pin "-") (pinfunction "-_-") (pintype "passive"))
      (node (ref "LED_MI") (pin "K") (pinfunction "C_K") (pintype "passive"))
      (node (ref "LED_MO") (pin "K") (pinfunction "C_K") (pintype "passive"))
      (node (ref "P1") (pin "1") (pinfunction "1_1") (pintype "passive"))
      (node (ref "P10") (pin "1") (pinfunction "1_1") (pintype "passive"))
      (node (ref "P11") (pin "1") (pinfunction "1_1") (pintype "passive"))
      (node (ref "P12") (pin "1") (pinfunction "1_1") (pintype "passive"))
      (node (ref "P13") (pin "1") (pinfunction "1_1") (pintype "passive"))
      (node (ref "P14") (pin "1") (pinfunction "1_1") (pintype "passive"))
      (node (ref "P15") (pin "1") (pinfunction "1_1") (pintype "passive"))
      (node (ref "P16") (pin "1") (pinfunction "1_1") (pintype "passive"))
      (node (ref "P2") (pin "1") (pinfunction "1_1") (pintype "passive"))
      (node (ref "P3") (pin "1") (pinfunction "1_1") (pintype "passive"))
      (node (ref "P4") (pin "1") (pinfunction "1_1") (pintype "passive"))
      (node (ref "P5") (pin "1") (pinfunction "1_1") (pintype "passive"))
      (node (ref "P6") (pin "1") (pinfunction "1_1") (pintype "passive"))
      (node (ref "P7") (pin "1") (pinfunction "1_1") (pintype "passive"))
      (node (ref "P8") (pin "1") (pinfunction "1_1") (pintype "passive"))
      (node (ref "P9") (pin "1") (pinfunction "1_1") (pintype "passive"))
      (node (ref "Q1") (pin "1") (pinfunction "E_1") (pintype "passive"))
      (node (ref "RESET") (pin "2") (pinfunction "2_2") (pintype "passive"))
      (node (ref "U2") (pin "21") (pinfunction "AGND_21") (pintype "bidirectional"))
      (node (ref "U2") (pin "3") (pinfunction "GND_3") (pintype "bidirectional"))
      (node (ref "U2") (pin "5") (pinfunction "GND_5") (pintype "bidirectional"))
      (node (ref "ULN2803A") (pin "9") (pinfunction "9_9") (pintype "bidirectional"))
      (node (ref "USB") (pin "4") (pinfunction "4_4") (pintype "passive"))
    )
    (net (code "3") (name "Net-(74HC238-A0)") (class "Default")
      (node (ref "74HC238") (pin "1") (pinfunction "A0_1") (pintype "input"))
      (node (ref "U2") (pin "28") (pinfunction "PC5(ADC5/SCL)_28") (pintype "bidirectional"))
    )
    (net (code "4") (name "Net-(74HC238-A1)") (class "Default")
      (node (ref "74HC238") (pin "2") (pinfunction "A1_2") (pintype "input"))
      (node (ref "U2") (pin "27") (pinfunction "PC4(ADC4/SDA)_27") (pintype "bidirectional"))
    )
    (net (code "5") (name "Net-(74HC238-A2)") (class "Default")
      (node (ref "74HC238") (pin "3") (pinfunction "A2_3") (pintype "input"))
      (node (ref "U2") (pin "26") (pinfunction "PC3(ADC3)_26") (pintype "bidirectional"))
    )
    (net (code "6") (name "Net-(74HC238-Y0)") (class "Default")
      (node (ref "74HC238") (pin "15") (pinfunction "Y0_15") (pintype "input"))
      (node (ref "ULN2803A") (pin "1") (pinfunction "1_1") (pintype "bidirectional"))
    )
    (net (code "7") (name "Net-(74HC238-Y1)") (class "Default")
      (node (ref "74HC238") (pin "14") (pinfunction "Y1_14") (pintype "input"))
      (node (ref "ULN2803A") (pin "2") (pinfunction "2_2") (pintype "bidirectional"))
    )
    (net (code "8") (name "Net-(74HC238-Y2)") (class "Default")
      (node (ref "74HC238") (pin "13") (pinfunction "Y2_13") (pintype "input"))
      (node (ref "ULN2803A") (pin "3") (pinfunction "3_3") (pintype "bidirectional"))
    )
    (net (code "9") (name "Net-(74HC238-Y3)") (class "Default")
      (node (ref "74HC238") (pin "12") (pinfunction "Y3_12") (pintype "input"))
      (node (ref "ULN2803A") (pin "4") (pinfunction "4_4") (pintype "bidirectional"))
    )
    (net (code "10") (name "Net-(74HC238-Y4)") (class "Default")
      (node (ref "74HC238") (pin "11") (pinfunction "Y4_11") (pintype "input"))
      (node (ref "ULN2803A") (pin "5") (pinfunction "5_5") (pintype "bidirectional"))
    )
    (net (code "11") (name "Net-(74HC238-Y5)") (class "Default")
      (node (ref "74HC238") (pin "10") (pinfunction "Y5_10") (pintype "input"))
      (node (ref "ULN2803A") (pin "6") (pinfunction "6_6") (pintype "bidirectional"))
    )
    (net (code "12") (name "Net-(74HC238-Y6)") (class "Default")
      (node (ref "74HC238") (pin "9") (pinfunction "Y6_9") (pintype "input"))
      (node (ref "ULN2803A") (pin "7") (pinfunction "7_7") (pintype "bidirectional"))
    )
    (net (code "13") (name "Net-(74HC238-Y7)") (class "Default")
      (node (ref "74HC238") (pin "7") (pinfunction "Y7_7") (pintype "input"))
      (node (ref "ULN2803A") (pin "8") (pinfunction "8_8") (pintype "bidirectional"))
    )
    (net (code "14") (name "Net-(4051_1-S0)") (class "Default")
      (node (ref "4051_1") (pin "11") (pinfunction "S0_11") (pintype "input"))
      (node (ref "4051_2") (pin "11") (pinfunction "S0_11") (pintype "input"))
      (node (ref "U2") (pin "23") (pinfunction "PC0(ADC0)_23") (pintype "bidirectional"))
    )
    (net (code "15") (name "Net-(4051_1-S1)") (class "Default")
      (node (ref "4051_1") (pin "10") (pinfunction "S1_10") (pintype "input"))
      (node (ref "4051_2") (pin "10") (pinfunction "S1_10") (pintype "input"))
      (node (ref "U2") (pin "24") (pinfunction "PC1(ADC1)_24") (pintype "bidirectional"))
    )
    (net (code "16") (name "Net-(4051_1-S2)") (class "Default")
      (node (ref "4051_1") (pin "9") (pinfunction "S2_9") (pintype "input"))
      (node (ref "4051_2") (pin "9") (pinfunction "S2_9") (pintype "input"))
      (node (ref "U2") (pin "25") (pinfunction "PC2(ADC2)_25") (pintype "bidirectional"))
    )
    (net (code "17") (name "Net-(4051_1-X0)") (class "Default")
      (node (ref "4051_1") (pin "13") (pinfunction "X0_13") (pintype "input"))
      (node (ref "P1") (pin "3") (pinfunction "3_3") (pintype "passive"))
    )
    (net (code "18") (name "Net-(4051_1-X1)") (class "Default")
      (node (ref "4051_1") (pin "14") (pinfunction "X1_14") (pintype "input"))
      (node (ref "P2") (pin "3") (pinfunction "3_3") (pintype "passive"))
    )
    (net (code "19") (name "Net-(4051_1-X2)") (class "Default")
      (node (ref "4051_1") (pin "15") (pinfunction "X2_15") (pintype "input"))
      (node (ref "P3") (pin "3") (pinfunction "3_3") (pintype "passive"))
    )
    (net (code "20") (name "Net-(4051_1-X3)") (class "Default")
      (node (ref "4051_1") (pin "12") (pinfunction "X3_12") (pintype "input"))
      (node (ref "P4") (pin "3") (pinfunction "3_3") (pintype "passive"))
    )
    (net (code "21") (name "Net-(4051_1-X4)") (class "Default")
      (node (ref "4051_1") (pin "1") (pinfunction "X4_1") (pintype "input"))
      (node (ref "P5") (pin "3") (pinfunction "3_3") (pintype "passive"))
    )
    (net (code "22") (name "Net-(4051_1-X5)") (class "Default")
      (node (ref "4051_1") (pin "5") (pinfunction "X5_5") (pintype "input"))
      (node (ref "P6") (pin "3") (pinfunction "3_3") (pintype "passive"))
    )
    (net (code "23") (name "Net-(4051_1-X6)") (class "Default")
      (node (ref "4051_1") (pin "2") (pinfunction "X6_2") (pintype "input"))
      (node (ref "P7") (pin "3") (pinfunction "3_3") (pintype "passive"))
    )
    (net (code "24") (name "Net-(4051_1-X7)") (class "Default")
      (node (ref "4051_1") (pin "4") (pinfunction "X7_4") (pintype "input"))
      (node (ref "P8") (pin "3") (pinfunction "3_3") (pintype "passive"))
    )
    (net (code "25") (name "Net-(4051_1-Z)") (class "Default")
      (node (ref "4051_1") (pin "3") (pinfunction "Z_3") (pintype "output"))
      (node (ref "U2") (pin "19") (pinfunction "ADC6_19") (pintype "bidirectional"))
    )
    (net (code "26") (name "Net-(4051_2-X0)") (class "Default")
      (node (ref "4051_2") (pin "13") (pinfunction "X0_13") (pintype "input"))
      (node (ref "P9") (pin "3") (pinfunction "3_3") (pintype "passive"))
    )
    (net (code "27") (name "Net-(4051_2-X1)") (class "Default")
      (node (ref "4051_2") (pin "14") (pinfunction "X1_14") (pintype "input"))
      (node (ref "P10") (pin "3") (pinfunction "3_3") (pintype "passive"))
    )
    (net (code "28") (name "Net-(4051_2-X2)") (class "Default")
      (node (ref "4051_2") (pin "15") (pinfunction "X2_15") (pintype "input"))
      (node (ref "P11") (pin "3") (pinfunction "3_3") (pintype "passive"))
    )
    (net (code "29") (name "Net-(4051_2-X3)") (class "Default")
      (node (ref "4051_2") (pin "12") (pinfunction "X3_12") (pintype "input"))
      (node (ref "P12") (pin "3") (pinfunction "3_3") (pintype "passive"))
    )
    (net (code "30") (name "Net-(4051_2-X4)") (class "Default")
      (node (ref "4051_2") (pin "1") (pinfunction "X4_1") (pintype "input"))
      (node (ref "P13") (pin "3") (pinfunction "3_3") (pintype "passive"))
    )
    (net (code "31") (name "Net-(4051_2-X5)") (class "Default")
      (node (ref "4051_2") (pin "5") (pinfunction "X5_5") (pintype "input"))
      (node (ref "P14") (pin "3") (pinfunction "3_3") (pintype "passive"))
    )
    (net (code "32") (name "Net-(4051_2-X6)") (class "Default")
      (node (ref "4051_2") (pin "2") (pinfunction "X6_2") (pintype "input"))
      (node (ref "P15") (pin "3") (pinfunction "3_3") (pintype "passive"))
    )
    (net (code "33") (name "Net-(4051_2-X7)") (class "Default")
      (node (ref "4051_2") (pin "4") (pinfunction "X7_4") (pintype "input"))
      (node (ref "P16") (pin "3") (pinfunction "3_3") (pintype "passive"))
    )
    (net (code "34") (name "Net-(4051_2-Z)") (class "Default")
      (node (ref "4051_2") (pin "3") (pinfunction "Z_3") (pintype "output"))
      (node (ref "U2") (pin "22") (pinfunction "ADC7_22") (pintype "bidirectional"))
    )
    (net (code "35") (name "Net-(ALTMUSTECH_AU123-LEDI)") (class "Default")
      (node (ref "ALTMUSTECH_AU123") (pin "14") (pinfunction "LEDI_14") (pintype "output"))
      (node (ref "R4") (pin "2") (pinfunction "2_2") (pintype "passive"))
    )
    (net (code "36") (name "Net-(ALTMUSTECH_AU123-LEDO)") (class "Default")
      (node (ref "ALTMUSTECH_AU123") (pin "13") (pinfunction "LEDO_13") (pintype "output"))
      (node (ref "R3") (pin "2") (pinfunction "2_2") (pintype "passive"))
    )
    (net (code "37") (name "Net-(ALTMUSTECH_AU123-MIN)") (class "Default")
      (node (ref "ALTMUSTECH_AU123") (pin "4") (pinfunction "MIN_4") (pintype "input"))
      (node (ref "U2") (pin "31") (pinfunction "PD1(TXD)_31") (pintype "bidirectional"))
    )
    (net (code "38") (name "Net-(ALTMUSTECH_AU123-MOUT)") (class "Default")
      (node (ref "ALTMUSTECH_AU123") (pin "3") (pinfunction "MOUT_3") (pintype "output"))
      (node (ref "R1") (pin "1") (pinfunction "1_1") (pintype "passive"))
    )
    (net (code "39") (name "Net-(ALTMUSTECH_AU123-V3)") (class "Default")
      (node (ref "ALTMUSTECH_AU123") (pin "5") (pinfunction "V3_5") (pintype "input"))
      (node (ref "C1") (pin "1") (pinfunction "1_1") (pintype "passive"))
    )
    (net (code "40") (name "Net-(ALTMUSTECH_AU123-VD+)") (class "Default")
      (node (ref "ALTMUSTECH_AU123") (pin "6") (pinfunction "VD+_6") (pintype "bidirectional"))
      (node (ref "USB") (pin "3") (pinfunction "3_3") (pintype "passive"))
    )
    (net (code "41") (name "Net-(ALTMUSTECH_AU123-VD-)") (class "Default")
      (node (ref "ALTMUSTECH_AU123") (pin "7") (pinfunction "VD-_7") (pintype "bidirectional"))
      (node (ref "USB") (pin "2") (pinfunction "2_2") (pintype "passive"))
    )
    (net (code "42") (name "Net-(ALTMUSTECH_AU123-XI)") (class "Default")
      (node (ref "ALTMUSTECH_AU123") (pin "9") (pinfunction "XI_9") (pintype "input"))
      (node (ref "C2") (pin "1") (pinfunction "1_1") (pintype "passive"))
      (node (ref "X1") (pin "2") (pinfunction "2_2") (pintype "passive"))
    )
    (net (code "43") (name "Net-(ALTMUSTECH_AU123-XO)") (class "Default")
      (node (ref "ALTMUSTECH_AU123") (pin "10") (pinfunction "XO_10") (pintype "output"))
      (node (ref "C3") (pin "1") (pinfunction "1_1") (pintype "passive"))
      (node (ref "X1") (pin "1") (pinfunction "1_1") (pintype "passive"))
    )
    (net (code "44") (name "Net-(D1-PadC)") (class "Default")
      (node (ref "D1") (pin "C") (pinfunction "C_C") (pintype "passive"))
      (node (ref "S1") (pin "1") (pinfunction "1_1") (pintype "passive"))
    )
    (net (code "45") (name "Net-(D2-PadC)") (class "Default")
      (node (ref "D2") (pin "C") (pinfunction "C_C") (pintype "passive"))
      (node (ref "S2") (pin "1") (pinfunction "1_1") (pintype "passive"))
    )
    (net (code "46") (name "Net-(D3-PadC)") (class "Default")
      (node (ref "D3") (pin "C") (pinfunction "C_C") (pintype "passive"))
      (node (ref "S3") (pin "1") (pinfunction "1_1") (pintype "passive"))
    )
    (net (code "47") (name "Net-(D4-PadC)") (class "Default")
      (node (ref "D4") (pin "C") (pinfunction "C_C") (pintype "passive"))
      (node (ref "S4") (pin "1") (pinfunction "1_1") (pintype "passive"))
    )
    (net (code "48") (name "Net-(D5-PadC)") (class "Default")
      (node (ref "D5") (pin "C") (pinfunction "C_C") (pintype "passive"))
      (node (ref "S5") (pin "1") (pinfunction "1_1") (pintype "passive"))
    )
    (net (code "49") (name "Net-(D6-PadC)") (class "Default")
      (node (ref "D6") (pin "C") (pinfunction "C_C") (pintype "passive"))
      (node (ref "S6") (pin "1") (pinfunction "1_1") (pintype "passive"))
    )
    (net (code "50") (name "Net-(D7-PadC)") (class "Default")
      (node (ref "D7") (pin "C") (pinfunction "C_C") (pintype "passive"))
      (node (ref "S7") (pin "1") (pinfunction "1_1") (pintype "passive"))
    )
    (net (code "51") (name "Net-(D8-PadC)") (class "Default")
      (node (ref "D8") (pin "C") (pinfunction "C_C") (pintype "passive"))
      (node (ref "S8") (pin "1") (pinfunction "1_1") (pintype "passive"))
    )
    (net (code "52") (name "Net-(D9-PadC)") (class "Default")
      (node (ref "D9") (pin "C") (pinfunction "C_C") (pintype "passive"))
      (node (ref "S9") (pin "1") (pinfunction "1_1") (pintype "passive"))
    )
    (net (code "53") (name "Net-(D10-PadC)") (class "Default")
      (node (ref "D10") (pin "C") (pinfunction "C_C") (pintype "passive"))
      (node (ref "S10") (pin "1") (pinfunction "1_1") (pintype "passive"))
    )
    (net (code "54") (name "Net-(D11-PadC)") (class "Default")
      (node (ref "D11") (pin "C") (pinfunction "C_C") (pintype "passive"))
      (node (ref "S11") (pin "1") (pinfunction "1_1") (pintype "passive"))
    )
    (net (code "55") (name "Net-(D12-PadC)") (class "Default")
      (node (ref "D12") (pin "C") (pinfunction "C_C") (pintype "passive"))
      (node (ref "S12") (pin "1") (pinfunction "1_1") (pintype "passive"))
    )
    (net (code "56") (name "Net-(D13-PadC)") (class "Default")
      (node (ref "D13") (pin "C") (pinfunction "C_C") (pintype "passive"))
      (node (ref "S13") (pin "1") (pinfunction "1_1") (pintype "passive"))
    )
    (net (code "57") (name "Net-(D14-PadC)") (class "Default")
      (node (ref "D14") (pin "C") (pinfunction "C_C") (pintype "passive"))
      (node (ref "S14") (pin "1") (pinfunction "1_1") (pintype "passive"))
    )
    (net (code "58") (name "Net-(D15-PadC)") (class "Default")
      (node (ref "D15") (pin "C") (pinfunction "C_C") (pintype "passive"))
      (node (ref "S15") (pin "1") (pinfunction "1_1") (pintype "passive"))
    )
    (net (code "59") (name "Net-(D16-PadC)") (class "Default")
      (node (ref "D16") (pin "C") (pinfunction "C_C") (pintype "passive"))
      (node (ref "S16") (pin "1") (pinfunction "1_1") (pintype "passive"))
    )
    (net (code "60") (name "Net-(D17-PadC)") (class "Default")
      (node (ref "D17") (pin "C") (pinfunction "C_C") (pintype "passive"))
      (node (ref "S17") (pin "1") (pinfunction "1_1") (pintype "passive"))
    )
    (net (code "61") (name "Net-(D18-PadC)") (class "Default")
      (node (ref "D18") (pin "C") (pinfunction "C_C") (pintype "passive"))
      (node (ref "S18") (pin "1") (pinfunction "1_1") (pintype "passive"))
    )
    (net (code "62") (name "Net-(D19-PadC)") (class "Default")
      (node (ref "D19") (pin "C") (pinfunction "C_C") (pintype "passive"))
      (node (ref "S19") (pin "1") (pinfunction "1_1") (pintype "passive"))
    )
    (net (code "63") (name "Net-(D20-PadC)") (class "Default")
      (node (ref "D20") (pin "C") (pinfunction "C_C") (pintype "passive"))
      (node (ref "S20") (pin "1") (pinfunction "1_1") (pintype "passive"))
    )
    (net (code "64") (name "Net-(D21-PadC)") (class "Default")
      (node (ref "D21") (pin "C") (pinfunction "C_C") (pintype "passive"))
      (node (ref "S21") (pin "1") (pinfunction "1_1") (pintype "passive"))
    )
    (net (code "65") (name "Net-(D22-PadC)") (class "Default")
      (node (ref "D22") (pin "C") (pinfunction "C_C") (pintype "passive"))
      (node (ref "S22") (pin "1") (pinfunction "1_1") (pintype "passive"))
    )
    (net (code "66") (name "Net-(D23-PadC)") (class "Default")
      (node (ref "D23") (pin "C") (pinfunction "C_C") (pintype "passive"))
      (node (ref "S23") (pin "1") (pinfunction "1_1") (pintype "passive"))
    )
    (net (code "67") (name "Net-(D24-PadC)") (class "Default")
      (node (ref "D24") (pin "C") (pinfunction "C_C") (pintype "passive"))
      (node (ref "S24") (pin "1") (pinfunction "1_1") (pintype "passive"))
    )
    (net (code "68") (name "Net-(D25-PadC)") (class "Default")
      (node (ref "D25") (pin "C") (pinfunction "C_C") (pintype "passive"))
      (node (ref "S25") (pin "1") (pinfunction "1_1") (pintype "passive"))
    )
    (net (code "69") (name "Net-(D26-PadC)") (class "Default")
      (node (ref "D26") (pin "C") (pinfunction "C_C") (pintype "passive"))
      (node (ref "S26") (pin "1") (pinfunction "1_1") (pintype "passive"))
    )
    (net (code "70") (name "Net-(D27-PadC)") (class "Default")
      (node (ref "D27") (pin "C") (pinfunction "C_C") (pintype "passive"))
      (node (ref "S27") (pin "1") (pinfunction "1_1") (pintype "passive"))
    )
    (net (code "71") (name "Net-(D28-PadC)") (class "Default")
      (node (ref "D28") (pin "C") (pinfunction "C_C") (pintype "passive"))
      (node (ref "S28") (pin "1") (pinfunction "1_1") (pintype "passive"))
    )
    (net (code "72") (name "Net-(D29-PadC)") (class "Default")
      (node (ref "D29") (pin "C") (pinfunction "C_C") (pintype "passive"))
      (node (ref "S29") (pin "1") (pinfunction "1_1") (pintype "passive"))
    )
    (net (code "73") (name "Net-(D30-PadC)") (class "Default")
      (node (ref "D30") (pin "C") (pinfunction "C_C") (pintype "passive"))
      (node (ref "S30") (pin "1") (pinfunction "1_1") (pintype "passive"))
    )
    (net (code "74") (name "Net-(D31-PadC)") (class "Default")
      (node (ref "D31") (pin "C") (pinfunction "C_C") (pintype "passive"))
      (node (ref "S31") (pin "1") (pinfunction "1_1") (pintype "passive"))
    )
    (net (code "75") (name "Net-(D32-PadC)") (class "Default")
      (node (ref "D32") (pin "C") (pinfunction "C_C") (pintype "passive"))
      (node (ref "S32") (pin "1") (pinfunction "1_1") (pintype "passive"))
    )
    (net (code "76") (name "Net-(LED1-PadA)") (class "Default")
      (node (ref "LED1") (pin "A") (pinfunction "A_A") (pintype "passive"))
      (node (ref "LED2") (pin "A") (pinfunction "A_A") (pintype "passive"))
      (node (ref "LED3") (pin "A") (pinfunction "A_A") (pintype "passive"))
      (node (ref "LED4") (pin "A") (pinfunction "A_A") (pintype "passive"))
      (node (ref "LED5") (pin "A") (pinfunction "A_A") (pintype "passive"))
      (node (ref "LED6") (pin "A") (pinfunction "A_A") (pintype "passive"))
      (node (ref "LED7") (pin "A") (pinfunction "A_A") (pintype "passive"))
      (node (ref "LED8") (pin "A") (pinfunction "A_A") (pintype "passive"))
      (node (ref "R6") (pin "1") (pinfunction "1_1") (pintype "passive"))
    )
    (net (code "77") (name "Net-(LED1-PadC)") (class "Default")
      (node (ref "LED1") (pin "C") (pinfunction "C_C") (pintype "passive"))
      (node (ref "LED17") (pin "C") (pinfunction "C_C") (pintype "passive"))
      (node (ref "LED25") (pin "C") (pinfunction "C_C") (pintype "passive"))
      (node (ref "LED9") (pin "C") (pinfunction "C_C") (pintype "passive"))
      (node (ref "S1") (pin "2") (pinfunction "2_2") (pintype "passive"))
      (node (ref "S17") (pin "2") (pinfunction "2_2") (pintype "passive"))
      (node (ref "S25") (pin "2") (pinfunction "2_2") (pintype "passive"))
      (node (ref "S9") (pin "2") (pinfunction "2_2") (pintype "passive"))
      (node (ref "ULN2803A") (pin "11") (pinfunction "11_11") (pintype "bidirectional"))
    )
    (net (code "78") (name "Net-(LED10-PadA)") (class "Default")
      (node (ref "LED10") (pin "A") (pinfunction "A_A") (pintype "passive"))
      (node (ref "LED11") (pin "A") (pinfunction "A_A") (pintype "passive"))
      (node (ref "LED12") (pin "A") (pinfunction "A_A") (pintype "passive"))
      (node (ref "LED13") (pin "A") (pinfunction "A_A") (pintype "passive"))
      (node (ref "LED14") (pin "A") (pinfunction "A_A") (pintype "passive"))
      (node (ref "LED15") (pin "A") (pinfunction "A_A") (pintype "passive"))
      (node (ref "LED16") (pin "A") (pinfunction "A_A") (pintype "passive"))
      (node (ref "LED9") (pin "A") (pinfunction "A_A") (pintype "passive"))
      (node (ref "R7") (pin "1") (pinfunction "1_1") (pintype "passive"))
    )
    (net (code "79") (name "Net-(LED10-PadC)") (class "Default")
      (node (ref "LED10") (pin "C") (pinfunction "C_C") (pintype "passive"))
      (node (ref "LED18") (pin "C") (pinfunction "C_C") (pintype "passive"))
      (node (ref "LED2") (pin "C") (pinfunction "C_C") (pintype "passive"))
      (node (ref "LED26") (pin "C") (pinfunction "C_C") (pintype "passive"))
      (node (ref "S10") (pin "2") (pinfunction "2_2") (pintype "passive"))
      (node (ref "S18") (pin "2") (pinfunction "2_2") (pintype "passive"))
      (node (ref "S2") (pin "2") (pinfunction "2_2") (pintype "passive"))
      (node (ref "S26") (pin "2") (pinfunction "2_2") (pintype "passive"))
      (node (ref "ULN2803A") (pin "12") (pinfunction "12_12") (pintype "bidirectional"))
    )
    (net (code "80") (name "Net-(LED11-PadC)") (class "Default")
      (node (ref "LED11") (pin "C") (pinfunction "C_C") (pintype "passive"))
      (node (ref "LED19") (pin "C") (pinfunction "C_C") (pintype "passive"))
      (node (ref "LED27") (pin "C") (pinfunction "C_C") (pintype "passive"))
      (node (ref "LED3") (pin "C") (pinfunction "C_C") (pintype "passive"))
      (node (ref "S11") (pin "2") (pinfunction "2_2") (pintype "passive"))
      (node (ref "S19") (pin "2") (pinfunction "2_2") (pintype "passive"))
      (node (ref "S27") (pin "2") (pinfunction "2_2") (pintype "passive"))
      (node (ref "S3") (pin "2") (pinfunction "2_2") (pintype "passive"))
      (node (ref "ULN2803A") (pin "13") (pinfunction "13_13") (pintype "bidirectional"))
    )
    (net (code "81") (name "Net-(LED12-PadC)") (class "Default")
      (node (ref "LED12") (pin "C") (pinfunction "C_C") (pintype "passive"))
      (node (ref "LED20") (pin "C") (pinfunction "C_C") (pintype "passive"))
      (node (ref "LED28") (pin "C") (pinfunction "C_C") (pintype "passive"))
      (node (ref "LED4") (pin "C") (pinfunction "C_C") (pintype "passive"))
      (node (ref "S12") (pin "2") (pinfunction "2_2") (pintype "passive"))
      (node (ref "S20") (pin "2") (pinfunction "2_2") (pintype "passive"))
      (node (ref "S28") (pin "2") (pinfunction "2_2") (pintype "passive"))
      (node (ref "S4") (pin "2") (pinfunction "2_2") (pintype "passive"))
      (node (ref "ULN2803A") (pin "14") (pinfunction "14_14") (pintype "bidirectional"))
    )
    (net (code "82") (name "Net-(LED13-PadC)") (class "Default")
      (node (ref "LED13") (pin "C") (pinfunction "C_C") (pintype "passive"))
      (node (ref "LED21") (pin "C") (pinfunction "C_C") (pintype "passive"))
      (node (ref "LED29") (pin "C") (pinfunction "C_C") (pintype "passive"))
      (node (ref "LED5") (pin "C") (pinfunction "C_C") (pintype "passive"))
      (node (ref "S13") (pin "2") (pinfunction "2_2") (pintype "passive"))
      (node (ref "S21") (pin "2") (pinfunction "2_2") (pintype "passive"))
      (node (ref "S29") (pin "2") (pinfunction "2_2") (pintype "passive"))
      (node (ref "S5") (pin "2") (pinfunction "2_2") (pintype "passive"))
      (node (ref "ULN2803A") (pin "15") (pinfunction "15_15") (pintype "bidirectional"))
    )
    (net (code "83") (name "Net-(LED14-PadC)") (class "Default")
      (node (ref "LED14") (pin "C") (pinfunction "C_C") (pintype "passive"))
      (node (ref "LED22") (pin "C") (pinfunction "C_C") (pintype "passive"))
      (node (ref "LED30") (pin "C") (pinfunction "C_C") (pintype "passive"))
      (node (ref "LED6") (pin "C") (pinfunction "C_C") (pintype "passive"))
      (node (ref "S14") (pin "2") (pinfunction "2_2") (pintype "passive"))
      (node (ref "S22") (pin "2") (pinfunction "2_2") (pintype "passive"))
      (node (ref "S30") (pin "2") (pinfunction "2_2") (pintype "passive"))
      (node (ref "S6") (pin "2") (pinfunction "2_2") (pintype "passive"))
      (node (ref "ULN2803A") (pin "16") (pinfunction "16_16") (pintype "bidirectional"))
    )
    (net (code "84") (name "Net-(LED15-PadC)") (class "Default")
      (node (ref "LED15") (pin "C") (pinfunction "C_C") (pintype "passive"))
      (node (ref "LED23") (pin "C") (pinfunction "C_C") (pintype "passive"))
      (node (ref "LED31") (pin "C") (pinfunction "C_C") (pintype "passive"))
      (node (ref "LED7") (pin "C") (pinfunction "C_C") (pintype "passive"))
      (node (ref "S15") (pin "2") (pinfunction "2_2") (pintype "passive"))
      (node (ref "S23") (pin "2") (pinfunction "2_2") (pintype "passive"))
      (node (ref "S31") (pin "2") (pinfunction "2_2") (pintype "passive"))
      (node (ref "S7") (pin "2") (pinfunction "2_2") (pintype "passive"))
      (node (ref "ULN2803A") (pin "17") (pinfunction "17_17") (pintype "bidirectional"))
    )
    (net (code "85") (name "Net-(LED16-PadC)") (class "Default")
      (node (ref "LED16") (pin "C") (pinfunction "C_C") (pintype "passive"))
      (node (ref "LED24") (pin "C") (pinfunction "C_C") (pintype "passive"))
      (node (ref "LED32") (pin "C") (pinfunction "C_C") (pintype "passive"))
      (node (ref "LED8") (pin "C") (pinfunction "C_C") (pintype "passive"))
      (node (ref "S16") (pin "2") (pinfunction "2_2") (pintype "passive"))
      (node (ref "S24") (pin "2") (pinfunction "2_2") (pintype "passive"))
      (node (ref "S32") (pin "2") (pinfunction "2_2") (pintype "passive"))
      (node (ref "S8") (pin "2") (pinfunction "2_2") (pintype "passive"))
      (node (ref "ULN2803A") (pin "18") (pinfunction "18_18") (pintype "bidirectional"))
    )
    (net (code "86") (name "Net-(LED17-PadA)") (class "Default")
      (node (ref "LED17") (pin "A") (pinfunction "A_A") (pintype "passive"))
      (node (ref "LED18") (pin "A") (pinfunction "A_A") (pintype "passive"))
      (node (ref "LED19") (pin "A") (pinfunction "A_A") (pintype "passive"))
      (node (ref "LED20") (pin "A") (pinfunction "A_A") (pintype "passive"))
      (node (ref "LED21") (pin "A") (pinfunction "A_A") (pintype "passive"))
      (node (ref "LED22") (pin "A") (pinfunction "A_A") (pintype "passive"))
      (node (ref "LED23") (pin "A") (pinfunction "A_A") (pintype "passive"))
      (node (ref "LED24") (pin "A") (pinfunction "A_A") (pintype "passive"))
      (node (ref "R8") (pin "1") (pinfunction "1_1") (pintype "passive"))
    )
    (net (code "87") (name "Net-(LED25-PadA)") (class "Default")
      (node (ref "LED25") (pin "A") (pinfunction "A_A") (pintype "passive"))
      (node (ref "LED26") (pin "A") (pinfunction "A_A") (pintype "passive"))
      (node (ref "LED27") (pin "A") (pinfunction "A_A") (pintype "passive"))
      (node (ref "LED28") (pin "A") (pinfunction "A_A") (pintype "passive"))
      (node (ref "LED29") (pin "A") (pinfunction "A_A") (pintype "passive"))
      (node (ref "LED30") (pin "A") (pinfunction "A_A") (pintype "passive"))
      (node (ref "LED31") (pin "A") (pinfunction "A_A") (pintype "passive"))
      (node (ref "LED32") (pin "A") (pinfunction "A_A") (pintype "passive"))
      (node (ref "R9") (pin "1") (pinfunction "1_1") (pintype "passive"))
    )
    (net (code "88") (name "Net-(LED_MI-PadA)") (class "Default")
      (node (ref "LED_MI") (pin "A") (pinfunction "A_A") (pintype "passive"))
      (node (ref "R4") (pin "1") (pinfunction "1_1") (pintype "passive"))
    )
    (net (code "89") (name "Net-(LED_MO-PadA)") (class "Default")
      (node (ref "LED_MO") (pin "A") (pinfunction "A_A") (pintype "passive"))
      (node (ref "R3") (pin "1") (pinfunction "1_1") (pintype "passive"))
    )
    (net (code "90") (name "Net-(Q1-B)") (class "Default")
      (node (ref "Q1") (pin "2") (pinfunction "B_2") (pintype "passive"))
      (node (ref "R1") (pin "2") (pinfunction "2_2") (pintype "passive"))
    )
    (net (code "91") (name "Net-(Q1-C)") (class "Default")
      (node (ref "Q1") (pin "3") (pinfunction "C_3") (pintype "passive"))
      (node (ref "R2") (pin "1") (pinfunction "1_1") (pintype "passive"))
      (node (ref "U2") (pin "30") (pinfunction "PD0(RXD)_30") (pintype "bidirectional"))
    )
    (net (code "92") (name "Net-(U2-AREF)") (class "Default")
      (node (ref "C13") (pin "1") (pinfunction "1_1") (pintype "passive"))
      (node (ref "U2") (pin "20") (pinfunction "AREF_20") (pintype "bidirectional"))
    )
    (net (code "93") (name "Net-(U2-AVCC)") (class "Default")
      (node (ref "C10") (pin "2") (pinfunction "2_2") (pintype "passive"))
      (node (ref "L1") (pin "2") (pinfunction "2_2") (pintype "passive"))
      (node (ref "U2") (pin "18") (pinfunction "AVCC_18") (pintype "bidirectional"))
    )
    (net (code "94") (name "Net-(U2-PB0(ICP))") (class "Default")
      (node (ref "R6") (pin "2") (pinfunction "2_2") (pintype "passive"))
      (node (ref "U2") (pin "12") (pinfunction "PB0(ICP)_12") (pintype "bidirectional"))
    )
    (net (code "95") (name "Net-(U2-PB1(OC1A))") (class "Default")
      (node (ref "R7") (pin "2") (pinfunction "2_2") (pintype "passive"))
      (node (ref "U2") (pin "13") (pinfunction "PB1(OC1A)_13") (pintype "bidirectional"))
    )
    (net (code "96") (name "Net-(U2-PB2(SS{slash}OC1B))") (class "Default")
      (node (ref "R8") (pin "2") (pinfunction "2_2") (pintype "passive"))
      (node (ref "U2") (pin "14") (pinfunction "PB2(SS/OC1B)_14") (pintype "bidirectional"))
    )
    (net (code "97") (name "Net-(U2-PB3(MOSI{slash}OC2))") (class "Default")
      (node (ref "R9") (pin "2") (pinfunction "2_2") (pintype "passive"))
      (node (ref "U2") (pin "15") (pinfunction "PB3(MOSI/OC2)_15") (pintype "bidirectional"))
    )
    (net (code "98") (name "Net-(U2-PB4(MISO))") (class "Default")
      (node (ref "ABCD") (pin "1") (pinfunction "1_1") (pintype "passive"))
      (node (ref "U2") (pin "16") (pinfunction "PB4(MISO)_16") (pintype "bidirectional"))
    )
    (net (code "99") (name "Net-(U2-PB5(SCK))") (class "Default")
      (node (ref "ABCD") (pin "2") (pinfunction "2_2") (pintype "passive"))
      (node (ref "U2") (pin "17") (pinfunction "PB5(SCK)_17") (pintype "bidirectional"))
    )
    (net (code "100") (name "Net-(U2-PB6(XTAL1{slash}TOSC1))") (class "Default")
      (node (ref "C11") (pin "2") (pinfunction "2_2") (pintype "passive"))
      (node (ref "U2") (pin "7") (pinfunction "PB6(XTAL1/TOSC1)_7") (pintype "bidirectional"))
      (node (ref "X2") (pin "1") (pinfunction "1_1") (pintype "passive"))
    )
    (net (code "101") (name "Net-(U2-PB7(XTAL2{slash}TOSC2))") (class "Default")
      (node (ref "C12") (pin "1") (pinfunction "1_1") (pintype "passive"))
      (node (ref "U2") (pin "8") (pinfunction "PB7(XTAL2/TOSC2)_8") (pintype "bidirectional"))
      (node (ref "X2") (pin "2") (pinfunction "2_2") (pintype "passive"))
    )
    (net (code "102") (name "Net-(U2-PC6({slash}RESET))") (class "Default")
      (node (ref "C16") (pin "2") (pinfunction "2_2") (pintype "passive"))
      (node (ref "R5") (pin "1") (pinfunction "1_1") (pintype "passive"))
      (node (ref "RESET") (pin "1") (pinfunction "1_1") (pintype "passive"))
      (node (ref "U2") (pin "29") (pinfunction "PC6(/RESET)_29") (pintype "bidirectional"))
    )
    (net (code "103") (name "Net-(U2-PD2(INT0))") (class "Default")
      (node (ref "ABCD") (pin "4") (pinfunction "4_4") (pintype "passive"))
      (node (ref "U2") (pin "32") (pinfunction "PD2(INT0)_32") (pintype "bidirectional"))
    )
    (net (code "104") (name "Net-(U2-PD3(INT1))") (class "Default")
      (node (ref "ABCD") (pin "3") (pinfunction "3_3") (pintype "passive"))
      (node (ref "U2") (pin "1") (pinfunction "PD3(INT1)_1") (pintype "bidirectional"))
    )
    (net (code "105") (name "Net-(U2-PD4(XCK{slash}T0))") (class "Default")
      (node (ref "D1") (pin "A") (pinfunction "A_A") (pintype "passive"))
      (node (ref "D2") (pin "A") (pinfunction "A_A") (pintype "passive"))
      (node (ref "D3") (pin "A") (pinfunction "A_A") (pintype "passive"))
      (node (ref "D4") (pin "A") (pinfunction "A_A") (pintype "passive"))
      (node (ref "D5") (pin "A") (pinfunction "A_A") (pintype "passive"))
      (node (ref "D6") (pin "A") (pinfunction "A_A") (pintype "passive"))
      (node (ref "D7") (pin "A") (pinfunction "A_A") (pintype "passive"))
      (node (ref "D8") (pin "A") (pinfunction "A_A") (pintype "passive"))
      (node (ref "U2") (pin "2") (pinfunction "PD4(XCK/T0)_2") (pintype "bidirectional"))
    )
    (net (code "106") (name "Net-(U2-PD5(T1))") (class "Default")
      (node (ref "D10") (pin "A") (pinfunction "A_A") (pintype "passive"))
      (node (ref "D11") (pin "A") (pinfunction "A_A") (pintype "passive"))
      (node (ref "D12") (pin "A") (pinfunction "A_A") (pintype "passive"))
      (node (ref "D13") (pin "A") (pinfunction "A_A") (pintype "passive"))
      (node (ref "D14") (pin "A") (pinfunction "A_A") (pintype "passive"))
      (node (ref "D15") (pin "A") (pinfunction "A_A") (pintype "passive"))
      (node (ref "D16") (pin "A") (pinfunction "A_A") (pintype "passive"))
      (node (ref "D9") (pin "A") (pinfunction "A_A") (pintype "passive"))
      (node (ref "U2") (pin "9") (pinfunction "PD5(T1)_9") (pintype "bidirectional"))
    )
    (net (code "107") (name "Net-(U2-PD6(AIN0))") (class "Default")
      (node (ref "D17") (pin "A") (pinfunction "A_A") (pintype "passive"))
      (node (ref "D18") (pin "A") (pinfunction "A_A") (pintype "passive"))
      (node (ref "D19") (pin "A") (pinfunction "A_A") (pintype "passive"))
      (node (ref "D20") (pin "A") (pinfunction "A_A") (pintype "passive"))
      (node (ref "D21") (pin "A") (pinfunction "A_A") (pintype "passive"))
      (node (ref "D22") (pin "A") (pinfunction "A_A") (pintype "passive"))
      (node (ref "D23") (pin "A") (pinfunction "A_A") (pintype "passive"))
      (node (ref "D24") (pin "A") (pinfunction "A_A") (pintype "passive"))
      (node (ref "U2") (pin "10") (pinfunction "PD6(AIN0)_10") (pintype "bidirectional"))
    )
    (net (code "108") (name "Net-(U2-PD7(AIN1))") (class "Default")
      (node (ref "D25") (pin "A") (pinfunction "A_A") (pintype "passive"))
      (node (ref "D26") (pin "A") (pinfunction "A_A") (pintype "passive"))
      (node (ref "D27") (pin "A") (pinfunction "A_A") (pintype "passive"))
      (node (ref "D28") (pin "A") (pinfunction "A_A") (pintype "passive"))
      (node (ref "D29") (pin "A") (pinfunction "A_A") (pintype "passive"))
      (node (ref "D30") (pin "A") (pinfunction "A_A") (pintype "passive"))
      (node (ref "D31") (pin "A") (pinfunction "A_A") (pintype "passive"))
      (node (ref "D32") (pin "A") (pinfunction "A_A") (pintype "passive"))
      (node (ref "U2") (pin "11") (pinfunction "PD7(AIN1)_11") (pintype "bidirectional"))
    )
    (net (code "109") (name "unconnected-(ALTMUSTECH_AU123-ACK-Pad16)") (class "Default")
      (node (ref "ALTMUSTECH_AU123") (pin "16") (pinfunction "ACK_16") (pintype "output"))
    )
    (net (code "110") (name "unconnected-(ALTMUSTECH_AU123-ACT#-Pad2)") (class "Default")
      (node (ref "ALTMUSTECH_AU123") (pin "2") (pinfunction "ACT#_2") (pintype "output"))
    )
    (net (code "111") (name "unconnected-(ALTMUSTECH_AU123-MUX-Pad15)") (class "Default")
      (node (ref "ALTMUSTECH_AU123") (pin "15") (pinfunction "MUX_15") (pintype "output"))
    )
    (net (code "112") (name "unconnected-(ALTMUSTECH_AU123-NC1-Pad18)") (class "Default")
      (node (ref "ALTMUSTECH_AU123") (pin "18") (pinfunction "NC1_18") (pintype "no_connect"))
    )
    (net (code "113") (name "unconnected-(ALTMUSTECH_AU123-NC2-Pad12)") (class "Default")
      (node (ref "ALTMUSTECH_AU123") (pin "12") (pinfunction "NC2_12") (pintype "no_connect"))
    )
    (net (code "114") (name "unconnected-(ALTMUSTECH_AU123-NC3-Pad11)") (class "Default")
      (node (ref "ALTMUSTECH_AU123") (pin "11") (pinfunction "NC3_11") (pintype "no_connect"))
    )
  )
)
